# chicker.net
KiCad netlist of a schematic drawn in Altium Designer
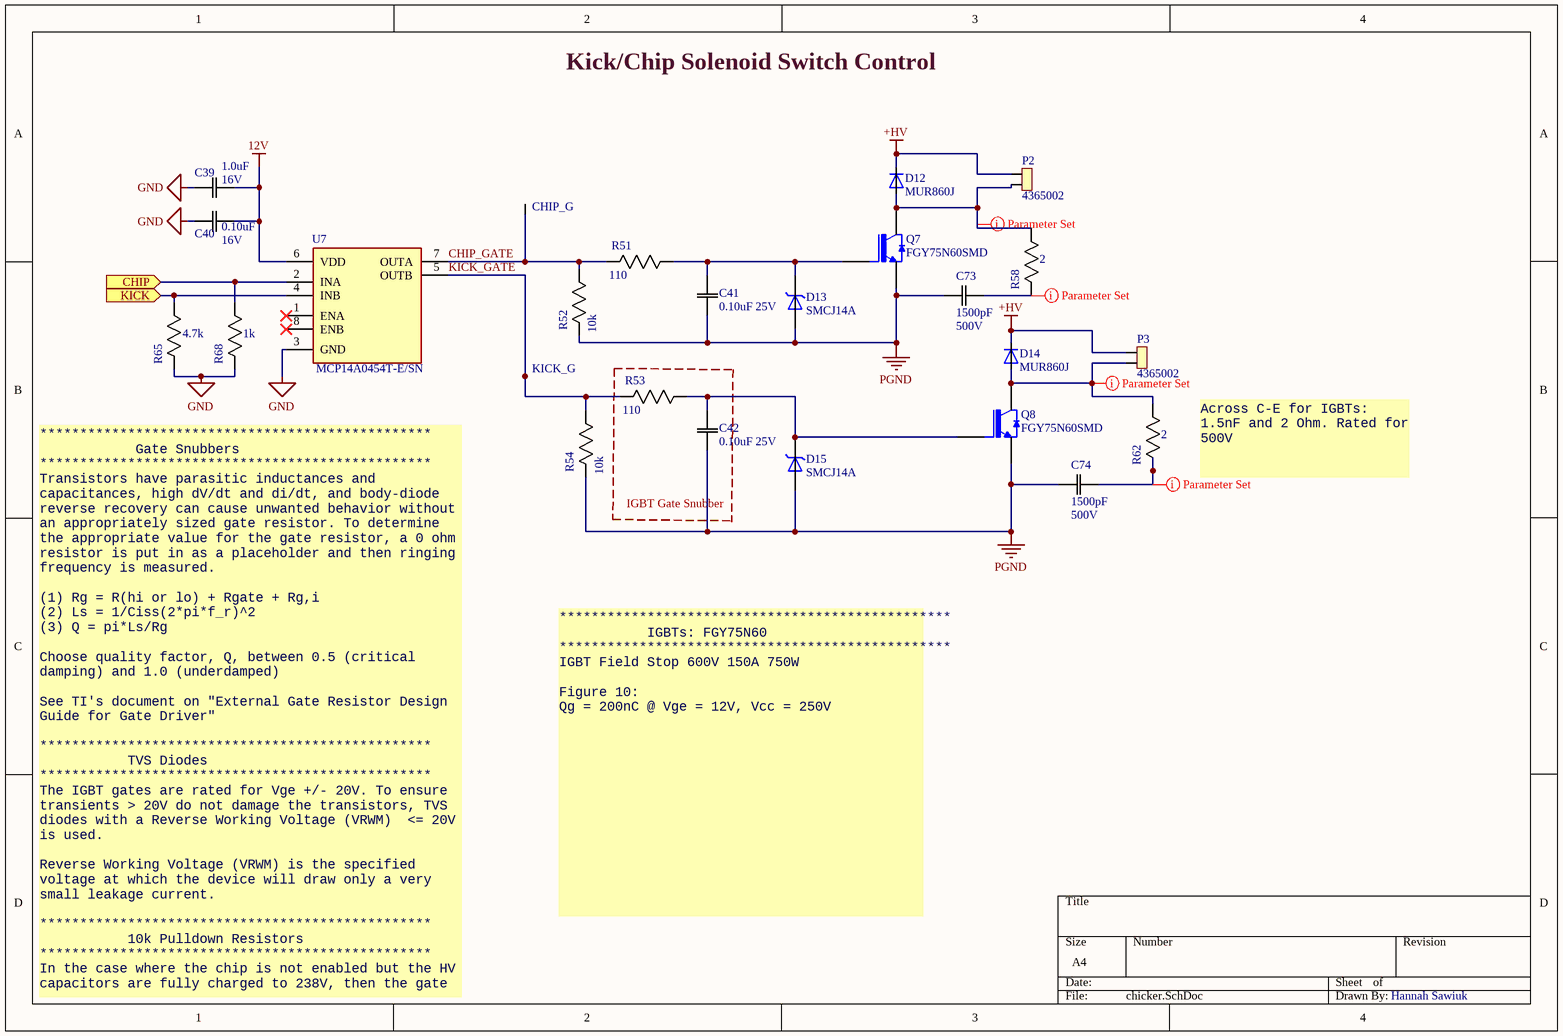
[diagram p0: chicker.SchDoc]

(export (version "E")
  (design (tool "Eeschema 10.0.6"))
  (components
    (comp (ref "C39")
      (value "1.0uF")
      (footprint "0603")
      (description "CAP CER 1.0UF 16V X5R 0603/0805")
      (fields
        (field (name "TOLERANCE") "10%")
        (field (name "RATING") "16V")
        (field (name "PART NUMBER") "CAP 1.0uF 16V")
      )
      (libsource (lib "capacitor_library") (part "CAP 1.0uF 16V"))
    )
    (comp (ref "C40")
      (value "0.10uF")
      (footprint "0603")
      (description "CAP CER 0.10UF 16V X5R 0603")
      (fields
        (field (name "TOLERANCE") "10%")
        (field (name "RATING") "16V")
        (field (name "PART NUMBER") "CAP 0.10uF 16V")
      )
      (libsource (lib "capacitor_library") (part "CAP 0.10uF 16V"))
    )
    (comp (ref "C41")
      (value "0.10uF 25V")
      (footprint "0805")
      (description "CAP CER 0.10UF 25V X7R 0805")
      (fields (field (name "TOLERANCE") "10%") (field (name "PART NUMBER") "CAP 0.10uF 25V"))
      (libsource (lib "capacitor_library") (part "CAP 0.10uF 25V"))
    )
    (comp (ref "C42")
      (value "0.10uF 25V")
      (footprint "0805")
      (description "CAP CER 0.10UF 25V X7R 0805")
      (fields (field (name "TOLERANCE") "10%") (field (name "PART NUMBER") "CAP 0.10uF 25V"))
      (libsource (lib "capacitor_library") (part "CAP 0.10uF 25V"))
    )
    (comp (ref "C73")
      (value "1500pF")
      (footprint "0805")
      (description "Default Symbol for Capacitors")
      (fields (field (name "RATING") "500V") (field (name "PART NUMBER") "CAP 1500pF 500V - 0805"))
      (libsource (lib "capacitor_library") (part "CAP_Default"))
    )
    (comp (ref "C74")
      (value "1500pF")
      (footprint "0805")
      (description "Default Symbol for Capacitors")
      (fields (field (name "RATING") "500V") (field (name "PART NUMBER") "CAP 1500pF 500V - 0805"))
      (libsource (lib "capacitor_library") (part "CAP_Default"))
    )
    (comp (ref "CHIP_G")
      (value "Test Point (Via)")
      (footprint "TP")
      (libsource (lib "IC_Library") (part "Test Point (Via)"))
    )
    (comp (ref "D12")
      (value "MUR860J")
      (footprint "DO-214AB-DIODES")
      (description "Diode Standard 600 V 8A Surface Mount SMC")
      (fields (field (name "PART NUMBER") "DIODE FAST 600V 8A"))
      (libsource (lib "Diode_Library") (part "DIODE FAST 600V 8A"))
    )
    (comp (ref "D13")
      (value "SMCJ14A")
      (footprint "DIOM7959X262N")
      (description "23.2V Clamp 64.7A Ipp Tvs Diode Surface Mount DO-214AB (SMC), VR = 14V, VBR = 15.6V")
      (fields (field (name "PART NUMBER") "DIODE TVS 14VR 15.6VBR"))
      (libsource (lib "Diode_Library") (part "DIODE TVS 14VR 15.6VBR"))
    )
    (comp (ref "D14")
      (value "MUR860J")
      (footprint "DO-214AB-DIODES")
      (description "Diode Standard 600 V 8A Surface Mount SMC")
      (fields (field (name "PART NUMBER") "DIODE FAST 600V 8A"))
      (libsource (lib "Diode_Library") (part "DIODE FAST 600V 8A"))
    )
    (comp (ref "D15")
      (value "SMCJ14A")
      (footprint "DIOM7959X262N")
      (description "23.2V Clamp 64.7A Ipp Tvs Diode Surface Mount DO-214AB (SMC), VR = 14V, VBR = 15.6V")
      (fields (field (name "PART NUMBER") "DIODE TVS 14VR 15.6VBR"))
      (libsource (lib "Diode_Library") (part "DIODE TVS 14VR 15.6VBR"))
    )
    (comp (ref "KICK_G")
      (value "Test Point (Via)")
      (footprint "TP")
      (libsource (lib "IC_Library") (part "Test Point (Via)"))
    )
    (comp (ref "P2")
      (value "4365002")
      (footprint "43650-02")
      (description "MOLEX MICROFIT 2CKT RIGHT THRU")
      (fields (field (name "MF") "MOLEX") (field (name "MP") "4365002XX"))
      (libsource (lib "Connector_Library") (part "CN MOLEX 4365002XX"))
    )
    (comp (ref "P3")
      (value "4365002")
      (footprint "43650-02")
      (description "MOLEX MICROFIT 2CKT RIGHT THRU")
      (fields (field (name "MF") "MOLEX") (field (name "MP") "4365002XX"))
      (libsource (lib "Connector_Library") (part "CN MOLEX 4365002XX"))
    )
    (comp (ref "Q7")
      (value "FGY75N60SMD")
      (footprint "TO-247-3 - FaceDown")
      (description "IGBT Field Stop 600V 150A 750W Through Hole PowerTO-247-3")
      (fields (field (name "MF") "ON Semiconductor"))
      (libsource (lib "Transistor_Library") (part "FGY75N60SMD"))
    )
    (comp (ref "Q8")
      (value "FGY75N60SMD")
      (footprint "TO-247-3 - FaceDown")
      (description "IGBT Field Stop 600V 150A 750W Through Hole PowerTO-247-3")
      (fields (field (name "MF") "ON Semiconductor"))
      (libsource (lib "Transistor_Library") (part "FGY75N60SMD"))
    )
    (comp (ref "R51")
      (value "110")
      (footprint "0603")
      (description "RES SMD 110 OHM 1% 1/8W 0603")
      (fields (field (name "TOLERANCE") "1%") (field (name "PART NUMBER") "RES 110.0 1/8W - 1%"))
      (libsource (lib "Resistor_Library") (part "RES 110.0 1/8W - 1%"))
    )
    (comp (ref "R52")
      (value "10k")
      (footprint "0603")
      (description "RES SMD 10K OHM 1% 1/8W 0603")
      (fields (field (name "TOLERANCE") "5%") (field (name "PART NUMBER") "RES 10k 1/8W - 1%"))
      (libsource (lib "Resistor_Library") (part "RES 10k 1/8W 1%"))
    )
    (comp (ref "R53")
      (value "110")
      (footprint "0603")
      (description "RES SMD 110 OHM 1% 1/8W 0603")
      (fields (field (name "TOLERANCE") "1%") (field (name "PART NUMBER") "RES 110.0 1/8W - 1%"))
      (libsource (lib "Resistor_Library") (part "RES 110.0 1/8W - 1%"))
    )
    (comp (ref "R54")
      (value "10k")
      (footprint "0603")
      (description "RES SMD 10K OHM 1% 1/8W 0603")
      (fields (field (name "TOLERANCE") "5%") (field (name "PART NUMBER") "RES 10k 1/8W - 1%"))
      (libsource (lib "Resistor_Library") (part "RES 10k 1/8W 1%"))
    )
    (comp (ref "R58")
      (value "2")
      (footprint "0603")
      (description "Default Resistor Symbol")
      (fields (field (name "TOLERANCE") "5%") (field (name "PART NUMBER") "RES 2.0 1/8W"))
      (libsource (lib "Resistor_Library") (part "RES_DEFAULT"))
    )
    (comp (ref "R62")
      (value "2")
      (footprint "0603")
      (description "Default Resistor Symbol")
      (fields (field (name "TOLERANCE") "5%") (field (name "PART NUMBER") "RES 2.0 1/8W"))
      (libsource (lib "Resistor_Library") (part "RES_DEFAULT"))
    )
    (comp (ref "R65")
      (value "4.7k")
      (footprint "0603")
      (description "Default Resistor Symbol")
      (fields (field (name "TOLERANCE") "5%") (field (name "PART NUMBER") "RES 4.7k 1/8W - 5%"))
      (libsource (lib "Resistor_Library") (part "RES_DEFAULT"))
    )
    (comp (ref "R68")
      (value "1k")
      (footprint "0603")
      (description "Default Resistor Symbol")
      (fields (field (name "TOLERANCE") "1%") (field (name "PART NUMBER") "RES 1k 1/8W"))
      (libsource (lib "Resistor_Library") (part "RES_DEFAULT"))
    )
    (comp (ref "U7")
      (value "MCP14A0454T-E/SN")
      (footprint "8-SOIC")
      (description "IC GATE DRVR LOW-SIDE 8SOIC")
      (fields (field (name "PART NUMBER") "MCP14A0454T-E_SN"))
      (libsource (lib "IC_Library") (part "MCP14A0454T-E/SN"))
    )
  )
  (nets
    (net (code "1") (name "+HV") (class "Default")
      (node (ref "D12") (pin "1") (pinfunction "C_1") (pintype "passive"))
      (node (ref "D14") (pin "1") (pinfunction "C_1") (pintype "passive"))
      (node (ref "P2") (pin "2") (pinfunction "2_2") (pintype "passive"))
      (node (ref "P3") (pin "2") (pinfunction "2_2") (pintype "passive"))
    )
    (net (code "2") (name "/CHIP") (class "Default")
      (node (ref "R68") (pin "1") (pinfunction "R1_1") (pintype "passive"))
      (node (ref "U7") (pin "2") (pinfunction "INA_2") (pintype "passive"))
    )
    (net (code "3") (name "/CHIP_GATE") (class "Default")
      (node (ref "CHIP_G") (pin "1") (pinfunction "1_1") (pintype "passive"))
      (node (ref "R51") (pin "2") (pinfunction "R2_2") (pintype "passive"))
      (node (ref "R52") (pin "1") (pinfunction "R1_1") (pintype "passive"))
      (node (ref "U7") (pin "7") (pinfunction "OUTA_7") (pintype "passive"))
    )
    (net (code "4") (name "/KICK") (class "Default")
      (node (ref "R65") (pin "1") (pinfunction "R1_1") (pintype "passive"))
      (node (ref "U7") (pin "4") (pinfunction "INB_4") (pintype "passive"))
    )
    (net (code "5") (name "/KICK_GATE") (class "Default")
      (node (ref "KICK_G") (pin "1") (pinfunction "1_1") (pintype "passive"))
      (node (ref "R53") (pin "2") (pinfunction "R2_2") (pintype "passive"))
      (node (ref "R54") (pin "1") (pinfunction "R1_1") (pintype "passive"))
      (node (ref "U7") (pin "5") (pinfunction "OUTB_5") (pintype "passive"))
    )
    (net (code "6") (name "12V") (class "Default")
      (node (ref "C39") (pin "2") (pinfunction "C2_2") (pintype "passive"))
      (node (ref "C40") (pin "2") (pinfunction "C2_2") (pintype "passive"))
      (node (ref "U7") (pin "6") (pinfunction "VDD_6") (pintype "passive"))
    )
    (net (code "7") (name "GND") (class "Default")
      (node (ref "C39") (pin "1") (pinfunction "C1_1") (pintype "passive"))
      (node (ref "C40") (pin "1") (pinfunction "C1_1") (pintype "passive"))
      (node (ref "R65") (pin "2") (pinfunction "R2_2") (pintype "passive"))
      (node (ref "R68") (pin "2") (pinfunction "R2_2") (pintype "passive"))
      (node (ref "U7") (pin "3") (pinfunction "GND_3") (pintype "passive"))
    )
    (net (code "8") (name "Net-(C41-C2)") (class "Default")
      (node (ref "C41") (pin "2") (pinfunction "C2_2") (pintype "passive"))
      (node (ref "D13") (pin "C") (pinfunction "C_C") (pintype "passive"))
      (node (ref "Q7") (pin "1") (pinfunction "G_1") (pintype "passive"))
      (node (ref "R51") (pin "1") (pinfunction "R1_1") (pintype "passive"))
    )
    (net (code "9") (name "Net-(C42-C2)") (class "Default")
      (node (ref "C42") (pin "2") (pinfunction "C2_2") (pintype "passive"))
      (node (ref "D15") (pin "C") (pinfunction "C_C") (pintype "passive"))
      (node (ref "Q8") (pin "1") (pinfunction "G_1") (pintype "passive"))
      (node (ref "R53") (pin "1") (pinfunction "R1_1") (pintype "passive"))
    )
    (net (code "10") (name "Net-(C73-C1)") (class "Default")
      (node (ref "C73") (pin "1") (pinfunction "C1_1") (pintype "passive"))
      (node (ref "R58") (pin "2") (pinfunction "R2_2") (pintype "passive"))
    )
    (net (code "11") (name "Net-(C74-C1)") (class "Default")
      (node (ref "C74") (pin "1") (pinfunction "C1_1") (pintype "passive"))
      (node (ref "R62") (pin "2") (pinfunction "R2_2") (pintype "passive"))
    )
    (net (code "12") (name "Net-(D12-A)") (class "Default")
      (node (ref "D12") (pin "2") (pinfunction "A_2") (pintype "passive"))
      (node (ref "P2") (pin "1") (pinfunction "1_1") (pintype "passive"))
      (node (ref "Q7") (pin "2") (pinfunction "C_2") (pintype "passive"))
      (node (ref "R58") (pin "1") (pinfunction "R1_1") (pintype "passive"))
    )
    (net (code "13") (name "Net-(D14-A)") (class "Default")
      (node (ref "D14") (pin "2") (pinfunction "A_2") (pintype "passive"))
      (node (ref "P3") (pin "1") (pinfunction "1_1") (pintype "passive"))
      (node (ref "Q8") (pin "2") (pinfunction "C_2") (pintype "passive"))
      (node (ref "R62") (pin "1") (pinfunction "R1_1") (pintype "passive"))
    )
    (net (code "14") (name "PGND") (class "Default")
      (node (ref "C41") (pin "1") (pinfunction "C1_1") (pintype "passive"))
      (node (ref "C42") (pin "1") (pinfunction "C1_1") (pintype "passive"))
      (node (ref "C73") (pin "2") (pinfunction "C2_2") (pintype "passive"))
      (node (ref "C74") (pin "2") (pinfunction "C2_2") (pintype "passive"))
      (node (ref "D13") (pin "A") (pinfunction "A_A") (pintype "passive"))
      (node (ref "D15") (pin "A") (pinfunction "A_A") (pintype "passive"))
      (node (ref "Q7") (pin "3") (pinfunction "E_3") (pintype "passive"))
      (node (ref "Q8") (pin "3") (pinfunction "E_3") (pintype "passive"))
      (node (ref "R52") (pin "2") (pinfunction "R2_2") (pintype "passive"))
      (node (ref "R54") (pin "2") (pinfunction "R2_2") (pintype "passive"))
    )
    (net (code "15") (name "unconnected-(U7-ENA-Pad1)") (class "Default")
      (node (ref "U7") (pin "1") (pinfunction "ENA_1") (pintype "passive+no_connect"))
    )
    (net (code "16") (name "unconnected-(U7-ENB-Pad8)") (class "Default")
      (node (ref "U7") (pin "8") (pinfunction "ENB_8") (pintype "passive+no_connect"))
    )
  )
)
